# POWER.net
KiCad netlist of a schematic drawn in Altium Designer
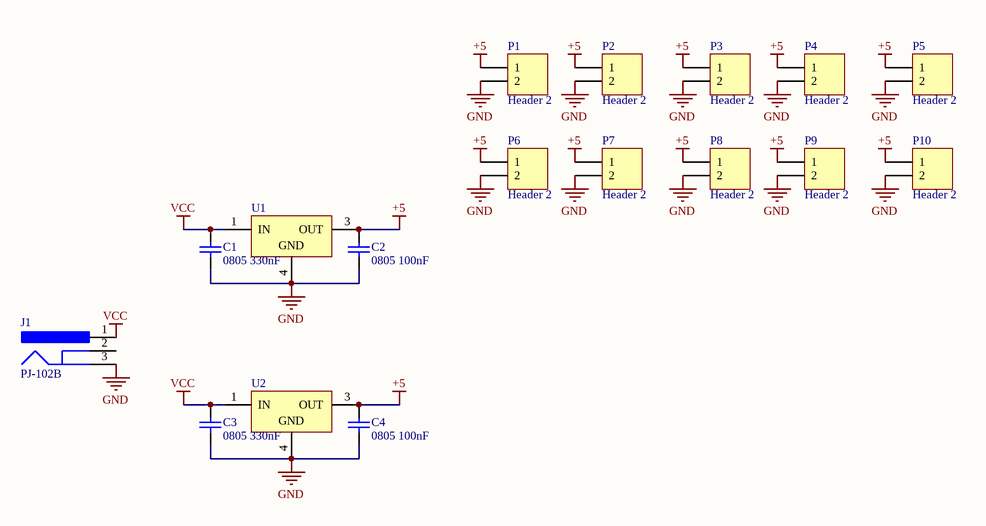
[diagram p0: POWER.SchDoc]

(export (version "E")
  (design (tool "Eeschema 10.0.6"))
  (components
    (comp (ref "C1")
      (value "0805 330nF")
      (footprint "CAPC0805(2012)100_L")
      (description "CAP 330nF 50V ±5% 0805 (2012 Metric) Thickness 1mm SMD")
      (fields (field (name "TOLERANCE") "Â±5%"))
      (libsource (lib "Altium Content Vault") (part "CAP"))
    )
    (comp (ref "C2")
      (value "0805 100nF")
      (footprint "CAPC0805(2012)100_M")
      (description "CAP 100nF 50V ±10% 0805 (2012 Metric) Thickness 1mm SMD")
      (fields (field (name "TOLERANCE") "Â±10%"))
      (libsource (lib "Altium Content Vault") (part "CAP"))
    )
    (comp (ref "C3")
      (value "0805 330nF")
      (footprint "CAPC0805(2012)100_L")
      (description "CAP 330nF 50V ±5% 0805 (2012 Metric) Thickness 1mm SMD")
      (fields (field (name "TOLERANCE") "Â±5%"))
      (libsource (lib "Altium Content Vault") (part "CAP"))
    )
    (comp (ref "C4")
      (value "0805 100nF")
      (footprint "CAPC0805(2012)100_M")
      (description "CAP 100nF 50V ±10% 0805 (2012 Metric) Thickness 1mm SMD")
      (fields (field (name "TOLERANCE") "Â±10%"))
      (libsource (lib "Altium Content Vault") (part "CAP"))
    )
    (comp (ref "J1")
      (value "PJ-102B")
      (footprint "CUI-PJ-102B_V")
      (fields (field (name "MANUFACTURER") "CUIInc."))
      (libsource (lib "Altium Content Vault") (part "JACK-2CD3-RN"))
    )
    (comp (ref "P1")
      (value "Header 2")
      (footprint "HDR1X2")
      (description "Header, 2-Pin")
      (fields (field (name "PUBLISHER") "Altium Limited"))
      (libsource (lib "Miscellaneous Connectors") (part "Header 2"))
    )
    (comp (ref "P2")
      (value "Header 2")
      (footprint "HDR1X2")
      (description "Header, 2-Pin")
      (fields (field (name "PUBLISHER") "Altium Limited"))
      (libsource (lib "Miscellaneous Connectors") (part "Header 2"))
    )
    (comp (ref "P3")
      (value "Header 2")
      (footprint "HDR1X2")
      (description "Header, 2-Pin")
      (fields (field (name "PUBLISHER") "Altium Limited"))
      (libsource (lib "Miscellaneous Connectors") (part "Header 2"))
    )
    (comp (ref "P4")
      (value "Header 2")
      (footprint "HDR1X2")
      (description "Header, 2-Pin")
      (fields (field (name "PUBLISHER") "Altium Limited"))
      (libsource (lib "Miscellaneous Connectors") (part "Header 2"))
    )
    (comp (ref "P5")
      (value "Header 2")
      (footprint "HDR1X2")
      (description "Header, 2-Pin")
      (fields (field (name "PUBLISHER") "Altium Limited"))
      (libsource (lib "Miscellaneous Connectors") (part "Header 2"))
    )
    (comp (ref "P6")
      (value "Header 2")
      (footprint "HDR1X2")
      (description "Header, 2-Pin")
      (fields (field (name "PUBLISHER") "Altium Limited"))
      (libsource (lib "Miscellaneous Connectors") (part "Header 2"))
    )
    (comp (ref "P7")
      (value "Header 2")
      (footprint "HDR1X2")
      (description "Header, 2-Pin")
      (fields (field (name "PUBLISHER") "Altium Limited"))
      (libsource (lib "Miscellaneous Connectors") (part "Header 2"))
    )
    (comp (ref "P8")
      (value "Header 2")
      (footprint "HDR1X2")
      (description "Header, 2-Pin")
      (fields (field (name "PUBLISHER") "Altium Limited"))
      (libsource (lib "Miscellaneous Connectors") (part "Header 2"))
    )
    (comp (ref "P9")
      (value "Header 2")
      (footprint "HDR1X2")
      (description "Header, 2-Pin")
      (fields (field (name "PUBLISHER") "Altium Limited"))
      (libsource (lib "Miscellaneous Connectors") (part "Header 2"))
    )
    (comp (ref "P10")
      (value "Header 2")
      (footprint "HDR1X2")
      (description "Header, 2-Pin")
      (fields (field (name "PUBLISHER") "Altium Limited"))
      (libsource (lib "Miscellaneous Connectors") (part "Header 2"))
    )
    (comp (ref "U1")
      (value "L7805ABD2T-TR")
      (footprint "TO-263_M")
      (description "Positive Voltage Regulator, 3-Pin D2PAK, Tape and Reel")
      (libsource (lib "Altium Content Vault") (part "PM-REG-L4940-SOT3"))
    )
    (comp (ref "U2")
      (value "L7805ABD2T-TR")
      (footprint "TO-263_M")
      (description "Positive Voltage Regulator, 3-Pin D2PAK, Tape and Reel")
      (libsource (lib "Altium Content Vault") (part "PM-REG-L4940-SOT3"))
    )
  )
  (nets
    (net (code "1") (name "+5") (class "Default")
      (node (ref "C2") (pin "2") (pinfunction "2_2") (pintype "passive"))
      (node (ref "C4") (pin "2") (pinfunction "2_2") (pintype "passive"))
      (node (ref "P1") (pin "1") (pinfunction "1_1") (pintype "passive"))
      (node (ref "P10") (pin "1") (pinfunction "1_1") (pintype "passive"))
      (node (ref "P2") (pin "1") (pinfunction "1_1") (pintype "passive"))
      (node (ref "P3") (pin "1") (pinfunction "1_1") (pintype "passive"))
      (node (ref "P4") (pin "1") (pinfunction "1_1") (pintype "passive"))
      (node (ref "P5") (pin "1") (pinfunction "1_1") (pintype "passive"))
      (node (ref "P6") (pin "1") (pinfunction "1_1") (pintype "passive"))
      (node (ref "P7") (pin "1") (pinfunction "1_1") (pintype "passive"))
      (node (ref "P8") (pin "1") (pinfunction "1_1") (pintype "passive"))
      (node (ref "P9") (pin "1") (pinfunction "1_1") (pintype "passive"))
      (node (ref "U1") (pin "3") (pinfunction "OUT_3") (pintype "power_in"))
      (node (ref "U2") (pin "3") (pinfunction "OUT_3") (pintype "power_in"))
    )
    (net (code "2") (name "GND") (class "Default")
      (node (ref "C1") (pin "2") (pinfunction "2_2") (pintype "passive"))
      (node (ref "C2") (pin "1") (pinfunction "1_1") (pintype "passive"))
      (node (ref "C3") (pin "2") (pinfunction "2_2") (pintype "passive"))
      (node (ref "C4") (pin "1") (pinfunction "1_1") (pintype "passive"))
      (node (ref "J1") (pin "3") (pinfunction "3_3") (pintype "passive"))
      (node (ref "P1") (pin "2") (pinfunction "2_2") (pintype "passive"))
      (node (ref "P10") (pin "2") (pinfunction "2_2") (pintype "passive"))
      (node (ref "P2") (pin "2") (pinfunction "2_2") (pintype "passive"))
      (node (ref "P3") (pin "2") (pinfunction "2_2") (pintype "passive"))
      (node (ref "P4") (pin "2") (pinfunction "2_2") (pintype "passive"))
      (node (ref "P5") (pin "2") (pinfunction "2_2") (pintype "passive"))
      (node (ref "P6") (pin "2") (pinfunction "2_2") (pintype "passive"))
      (node (ref "P7") (pin "2") (pinfunction "2_2") (pintype "passive"))
      (node (ref "P8") (pin "2") (pinfunction "2_2") (pintype "passive"))
      (node (ref "P9") (pin "2") (pinfunction "2_2") (pintype "passive"))
      (node (ref "U1") (pin "4") (pinfunction "GND_4") (pintype "power_in"))
      (node (ref "U2") (pin "4") (pinfunction "GND_4") (pintype "power_in"))
    )
    (net (code "3") (name "VCC") (class "Default")
      (node (ref "C1") (pin "1") (pinfunction "1_1") (pintype "passive"))
      (node (ref "C3") (pin "1") (pinfunction "1_1") (pintype "passive"))
      (node (ref "J1") (pin "1") (pinfunction "1_1") (pintype "passive"))
      (node (ref "U1") (pin "1") (pinfunction "IN_1") (pintype "power_in"))
      (node (ref "U2") (pin "1") (pinfunction "IN_1") (pintype "power_in"))
    )
    (net (code "4") (name "unconnected-(J1-Pad2)") (class "Default")
      (node (ref "J1") (pin "2") (pinfunction "2_2") (pintype "passive"))
    )
  )
)
